# XDS100V2_EMULATOR.net
KiCad netlist of a schematic drawn in Altium Designer
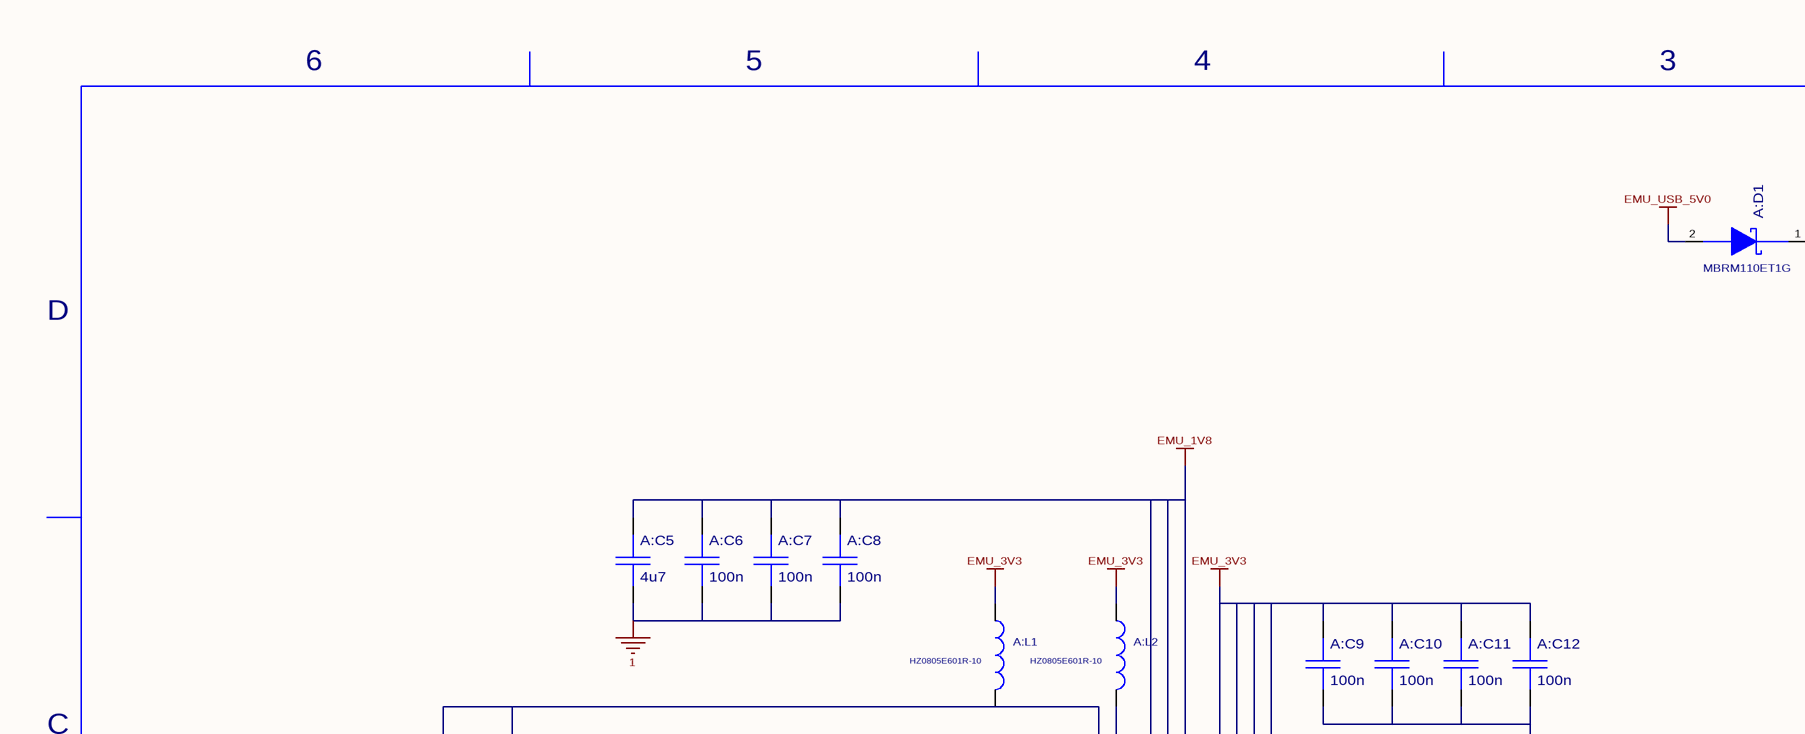
[diagram p0: XDS100V2_EMULATOR.SchDoc, top left]
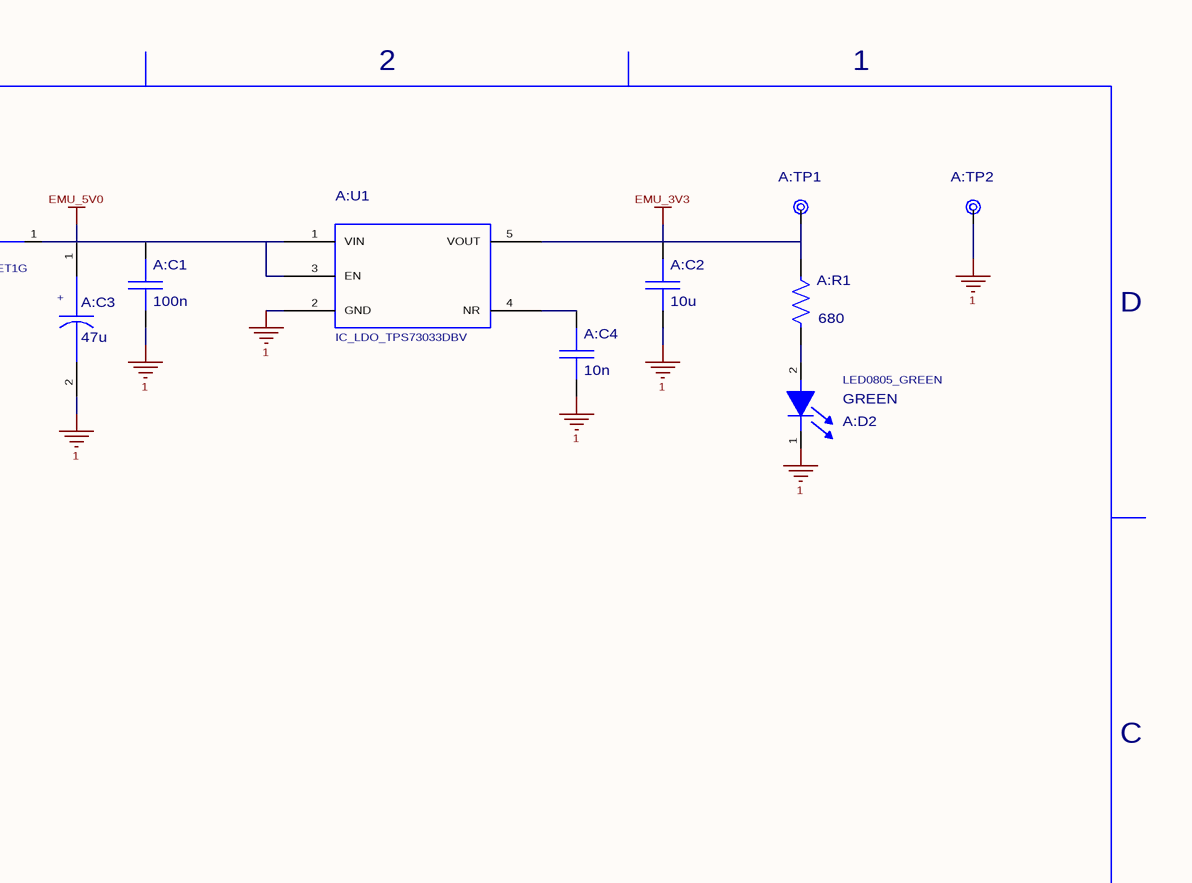
[diagram p1: XDS100V2_EMULATOR.SchDoc, top right]
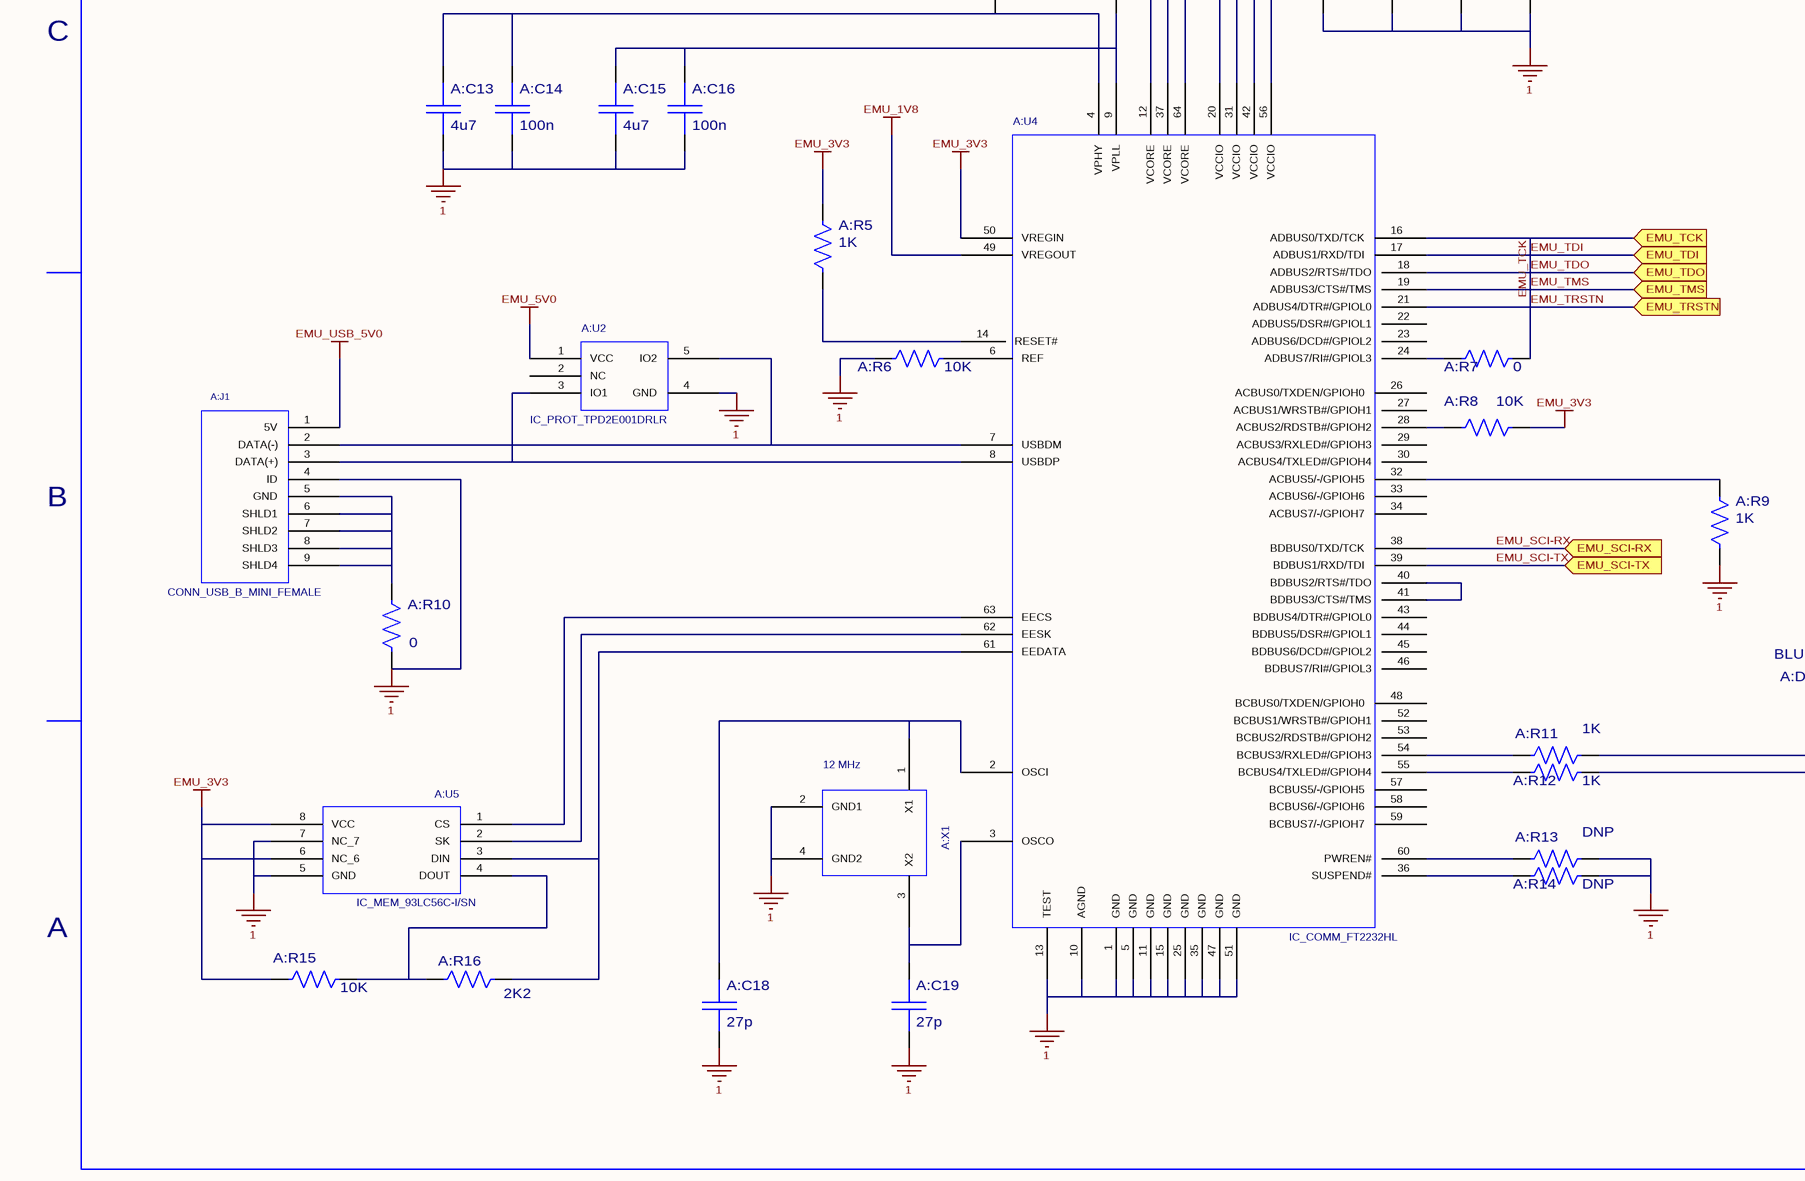
[diagram p2: XDS100V2_EMULATOR.SchDoc, bottom left]
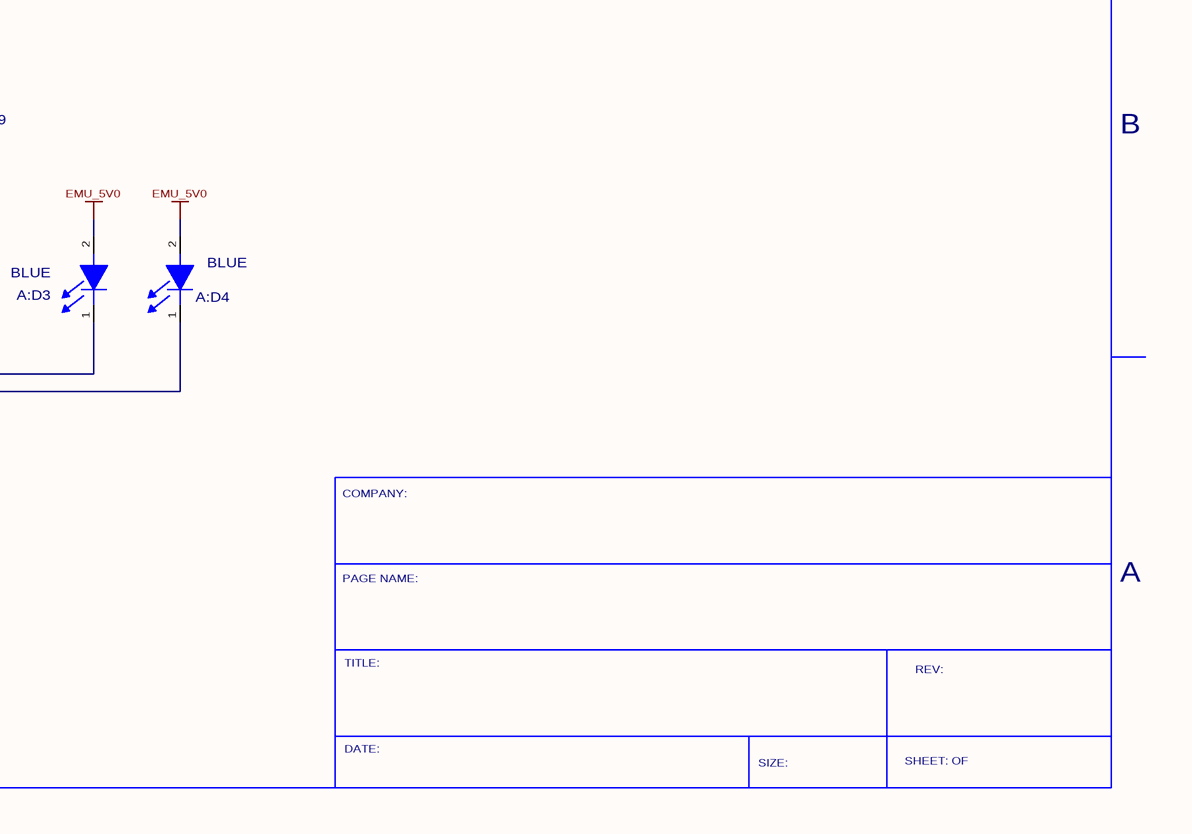
[diagram p3: XDS100V2_EMULATOR.SchDoc, bottom right]

(export (version "E")
  (design (tool "Eeschema 10.0.6"))
  (components
    (comp (ref "A:C1")
      (value "100n")
      (footprint "C0402")
      (description "CAP CER 16V 10% X7R 0402")
      (fields (field (name "Comment") "C0402_16V_X7R"))
      (libsource (lib "*") (part "C0402_16V_X7R"))
    )
    (comp (ref "A:C2")
      (value "10u")
      (footprint "C0603")
      (description "CAP CER 6.3V 20% X5R 0603")
      (fields (field (name "Comment") "C0603_16V_X7R"))
      (libsource (lib "*") (part "C0603_16V_X7R"))
    )
    (comp (ref "A:C3")
      (value "47u")
      (footprint "C0805P")
      (description "CAP TANT 20% 0805 6.3V")
      (fields (field (name "PART NUMBER") "TCTP0J476M8R") (field (name "Comment") "C0805_10V_TANT"))
      (libsource (lib "*") (part "C0805_10V_TANT"))
    )
    (comp (ref "A:C4")
      (value "10n")
      (footprint "C0402")
      (description "CAP CER 16V 10% X7R 0402")
      (fields (field (name "Comment") "C0402_16V_X7R"))
      (libsource (lib "*") (part "C0402_16V_X7R"))
    )
    (comp (ref "A:C5")
      (value "4u7")
      (footprint "C0603")
      (description "CAP CER 6.3V 10% X5R 0603")
      (fields (field (name "Comment") "C0603_16V_X7R"))
      (libsource (lib "*") (part "C0603_16V_X7R"))
    )
    (comp (ref "A:C6")
      (value "100n")
      (footprint "C0402")
      (description "CAP CER 16V 10% X7R 0402")
      (fields (field (name "Comment") "C0402_16V_X7R"))
      (libsource (lib "*") (part "C0402_16V_X7R"))
    )
    (comp (ref "A:C7")
      (value "100n")
      (footprint "C0402")
      (description "CAP CER 16V 10% X7R 0402")
      (fields (field (name "Comment") "C0402_16V_X7R"))
      (libsource (lib "*") (part "C0402_16V_X7R"))
    )
    (comp (ref "A:C8")
      (value "100n")
      (footprint "C0402")
      (description "CAP CER 16V 10% X7R 0402")
      (fields (field (name "Comment") "C0402_16V_X7R"))
      (libsource (lib "*") (part "C0402_16V_X7R"))
    )
    (comp (ref "A:C9")
      (value "100n")
      (footprint "C0402")
      (description "CAP CER 16V 10% X7R 0402")
      (fields (field (name "Comment") "C0402_16V_X7R"))
      (libsource (lib "*") (part "C0402_16V_X7R"))
    )
    (comp (ref "A:C10")
      (value "100n")
      (footprint "C0402")
      (description "CAP CER 16V 10% X7R 0402")
      (fields (field (name "Comment") "C0402_16V_X7R"))
      (libsource (lib "*") (part "C0402_16V_X7R"))
    )
    (comp (ref "A:C11")
      (value "100n")
      (footprint "C0402")
      (description "CAP CER 16V 10% X7R 0402")
      (fields (field (name "Comment") "C0402_16V_X7R"))
      (libsource (lib "*") (part "C0402_16V_X7R"))
    )
    (comp (ref "A:C12")
      (value "100n")
      (footprint "C0402")
      (description "CAP CER 16V 10% X7R 0402")
      (fields (field (name "Comment") "C0402_16V_X7R"))
      (libsource (lib "*") (part "C0402_16V_X7R"))
    )
    (comp (ref "A:C13")
      (value "4u7")
      (footprint "C0603")
      (description "CAP CER 6.3V 10% X5R 0603")
      (fields (field (name "Comment") "C0603_16V_X7R"))
      (libsource (lib "*") (part "C0603_16V_X7R"))
    )
    (comp (ref "A:C14")
      (value "100n")
      (footprint "C0402")
      (description "CAP CER 16V 10% X7R 0402")
      (fields (field (name "Comment") "C0402_16V_X7R"))
      (libsource (lib "*") (part "C0402_16V_X7R"))
    )
    (comp (ref "A:C15")
      (value "4u7")
      (footprint "C0603")
      (description "CAP CER 6.3V 10% X5R 0603")
      (fields (field (name "Comment") "C0603_16V_X7R"))
      (libsource (lib "*") (part "C0603_16V_X7R"))
    )
    (comp (ref "A:C16")
      (value "100n")
      (footprint "C0402")
      (description "CAP CER 16V 10% X7R 0402")
      (fields (field (name "Comment") "C0402_16V_X7R"))
      (libsource (lib "*") (part "C0402_16V_X7R"))
    )
    (comp (ref "A:C18")
      (value "27p")
      (footprint "C0402")
      (description "CAP CER 50V NP0 0402")
      (fields (field (name "Comment") "C0402_50V_NP0"))
      (libsource (lib "*") (part "C0402_50V_NP0"))
    )
    (comp (ref "A:C19")
      (value "27p")
      (footprint "C0402")
      (description "CAP CER 50V NP0 0402")
      (fields (field (name "Comment") "C0402_50V_NP0"))
      (libsource (lib "*") (part "C0402_50V_NP0"))
    )
    (comp (ref "A:D1")
      (value "DIODE_SCHOTTKY_MBRM110ET1G")
      (footprint "DO-216AA")
      (description "DIODE SCHOTTKY 10V 1A POWERMITE")
      (fields (field (name "PART NUMBER") "MBRM110ET1G") (field (name "MANUFACTURER") "On Semiconductor"))
      (libsource (lib "*") (part "DIODE_SCHOTTKY_MBRM110ET1G"))
    )
    (comp (ref "A:D2")
      (value "LED0805_GREEN")
      (footprint "LED0805")
      (description "LED GREEN 0805 SMD, Diffused, 567nm")
      (fields (field (name "ALTIUM_VALUE") "GREEN"))
      (libsource (lib "*") (part "LED0805_GREEN"))
    )
    (comp (ref "A:D3")
      (value "BLUE")
      (footprint "LED0805")
      (description "LED BLUE 0805 SMD, Clear, 470nm")
      (fields (field (name "Comment") "LED0805_BLUE"))
      (libsource (lib "*") (part "LED0805_BLUE"))
    )
    (comp (ref "A:D4")
      (value "BLUE")
      (footprint "LED0805")
      (description "LED BLUE 0805 SMD, Clear, 470nm")
      (fields (field (name "Comment") "LED0805_BLUE"))
      (libsource (lib "*") (part "LED0805_BLUE"))
    )
    (comp (ref "A:J1")
      (value "CONN_USB_B_MINI_FEMALE")
      (footprint "CONN_USB_B_MINI_FEMALE")
      (description "CONN RECEPT MINI USB2.0 5POS")
      (fields (field (name "PART NUMBER") "UX60-MB-5ST"))
      (libsource (lib "*") (part "CONN_USB_B_MINI_FEMALE"))
    )
    (comp (ref "A:L1")
      (value "L0805_HZ0805E601R-10")
      (footprint "L0805")
      (description "FERRITE 500MA 600 OHM 0805 SMD")
      (fields (field (name "PART NUMBER") "HZ0805E601R-10"))
      (libsource (lib "*") (part "L0805_HZ0805E601R-10"))
    )
    (comp (ref "A:L2")
      (value "L0805_HZ0805E601R-10")
      (footprint "L0805")
      (description "FERRITE 500MA 600 OHM 0805 SMD")
      (fields (field (name "PART NUMBER") "HZ0805E601R-10"))
      (libsource (lib "*") (part "L0805_HZ0805E601R-10"))
    )
    (comp (ref "A:R1")
      (value "680")
      (footprint "R0402")
      (description "RES 1/16W 5% 0402 SMD")
      (fields (field (name "Comment") "R0402_5%"))
      (libsource (lib "") (part "R0402_5%_1"))
    )
    (comp (ref "A:R5")
      (value "1K")
      (footprint "R0402")
      (description "RES 1/16W 5% 0402 SMD")
      (fields (field (name "Comment") "R0402_5%"))
      (libsource (lib "") (part "R0402_5%_1"))
    )
    (comp (ref "A:R6")
      (value "10K")
      (footprint "R0402")
      (description "RES 1/16W 5% 0402 SMD")
      (fields (field (name "Comment") "R0402_5%"))
      (libsource (lib "*") (part "R0402_5%"))
    )
    (comp (ref "A:R7")
      (value "0")
      (footprint "R0402")
      (description "RES 1/16W 5% 0402 SMD")
      (fields (field (name "Comment") "R0402_5%"))
      (libsource (lib "*") (part "R0402_5%"))
    )
    (comp (ref "A:R8")
      (value "10K")
      (footprint "R0402")
      (description "RES 1/16W 5% 0402 SMD")
      (fields (field (name "Comment") "R0402_5%"))
      (libsource (lib "*") (part "R0402_5%"))
    )
    (comp (ref "A:R9")
      (value "1K")
      (footprint "R0402")
      (description "RES 1/16W 5% 0402 SMD")
      (fields (field (name "Comment") "R0402_5%"))
      (libsource (lib "") (part "R0402_5%_1"))
    )
    (comp (ref "A:R10")
      (value "0")
      (footprint "R0402")
      (description "RES 1/16W 5% 0402 SMD")
      (fields (field (name "Comment") "R0402_5%"))
      (libsource (lib "") (part "R0402_5%_1"))
    )
    (comp (ref "A:R11")
      (value "1K")
      (footprint "R0402")
      (description "RES 1/16W 5% 0402 SMD")
      (fields (field (name "Comment") "R0402_5%"))
      (libsource (lib "*") (part "R0402_5%"))
    )
    (comp (ref "A:R12")
      (value "1K")
      (footprint "R0402")
      (description "RES 1/16W 5% 0402 SMD")
      (fields (field (name "Comment") "R0402_5%"))
      (libsource (lib "*") (part "R0402_5%"))
    )
    (comp (ref "A:R13")
      (value "DNP")
      (footprint "R0402")
      (description "RES 1/16W 5% 0402 SMD")
      (fields (field (name "Comment") "R0402_5%"))
      (libsource (lib "*") (part "R0402_5%"))
    )
    (comp (ref "A:R14")
      (value "DNP")
      (footprint "R0402")
      (description "RES 1/16W 5% 0402 SMD")
      (fields (field (name "Comment") "R0402_5%"))
      (libsource (lib "*") (part "R0402_5%"))
    )
    (comp (ref "A:R15")
      (value "10K")
      (footprint "R0402")
      (description "RES 1/16W 5% 0402 SMD")
      (fields (field (name "Comment") "R0402_5%"))
      (libsource (lib "*") (part "R0402_5%"))
    )
    (comp (ref "A:R16")
      (value "2K2")
      (footprint "R0402")
      (description "RES 1/16W 5% 0402 SMD")
      (fields (field (name "Comment") "R0402_5%"))
      (libsource (lib "") (part "R0402_5%_1"))
    )
    (comp (ref "A:TP1")
      (value "VIA_20_40")
      (footprint "VIA_20_40")
      (description "Via, 20 ID, 40 OD (mil)")
      (libsource (lib "*") (part "VIA_20_40"))
    )
    (comp (ref "A:TP2")
      (value "VIA_20_40")
      (footprint "VIA_20_40")
      (description "Via, 20 ID, 40 OD (mil)")
      (libsource (lib "*") (part "VIA_20_40"))
    )
    (comp (ref "A:U1")
      (value "IC_LDO_TPS73033DBV")
      (footprint "SOT-23-5")
      (description "IC LDO REG HI-PSRR 3.3V SOT23-5")
      (fields (field (name "PART NUMBER") "TPS73033DBV"))
      (libsource (lib "*") (part "IC_LDO_TPS73033DBV"))
    )
    (comp (ref "A:U2")
      (value "IC_PROT_TPD2E001DRLR")
      (footprint "SOT-553-5")
      (description "IC ESD-PROT ARRAY 2CH SOT-5")
      (fields (field (name "PART NUMBER") "TPD2E001DRLR"))
      (libsource (lib "*") (part "IC_PROT_TPD2E001DRLR"))
    )
    (comp (ref "A:U4")
      (value "IC_COMM_FT2232HL")
      (footprint "QFN-64")
      (description "IC USB HS DUAL UART/FIFO 64-QFN")
      (fields (field (name "PART NUMBER") "FT2232HL"))
      (libsource (lib "*") (part "IC_COMM_FT2232HL"))
    )
    (comp (ref "A:U5")
      (value "IC_MEM_93LC56C-I/SN")
      (footprint "SOIC-8")
      (description "IC EEPROM 2KBIT 3MHZ 8SOIC")
      (fields (field (name "PART NUMBER") "93LC56C-I/SN"))
      (libsource (lib "*") (part "IC_MEM_93LC56C-I/SN"))
    )
    (comp (ref "A:X1")
      (value "12 MHz")
      (footprint "OSC_ECS-120-20-30B")
      (description "CRYSTAL 12.000 MHZ 20PF SMD")
      (fields
        (field (name "PART NUMBER") "ECS-120-20-30B-TR")
        (field (name "Comment") "OSC_ECS-120-20-30B-TR")
      )
      (libsource (lib "*") (part "OSC_ECS-120-20-30B-TR"))
    )
  )
  (nets
    (net (code "1") (name "/EMU_SCI-RX") (class "Default")
      (node (ref "A:U4") (pin "38") (pinfunction "BDBUS0/TXD/TCK_38") (pintype "passive"))
    )
    (net (code "2") (name "/EMU_SCI-TX") (class "Default")
      (node (ref "A:U4") (pin "39") (pinfunction "BDBUS1/RXD/TDI_39") (pintype "passive"))
    )
    (net (code "3") (name "/EMU_TCK") (class "Default")
      (node (ref "A:R7") (pin "2") (pinfunction "2_2") (pintype "passive"))
      (node (ref "A:U4") (pin "16") (pinfunction "ADBUS0/TXD/TCK_16") (pintype "passive"))
      (node (ref "A:U4") (pin "17") (pinfunction "ADBUS1/RXD/TDI_17") (pintype "passive"))
      (node (ref "A:U4") (pin "18") (pinfunction "ADBUS2/RTS#/TDO_18") (pintype "passive"))
      (node (ref "A:U4") (pin "19") (pinfunction "ADBUS3/CTS#/TMS_19") (pintype "passive"))
      (node (ref "A:U4") (pin "21") (pinfunction "ADBUS4/DTR#/GPIOL0_21") (pintype "passive"))
    )
    (net (code "4") (name "1") (class "Default")
      (node (ref "A:C1") (pin "1") (pinfunction "1_1") (pintype "passive"))
      (node (ref "A:C10") (pin "1") (pinfunction "1_1") (pintype "passive"))
      (node (ref "A:C11") (pin "1") (pinfunction "1_1") (pintype "passive"))
      (node (ref "A:C12") (pin "1") (pinfunction "1_1") (pintype "passive"))
      (node (ref "A:C13") (pin "1") (pinfunction "1_1") (pintype "passive"))
      (node (ref "A:C14") (pin "1") (pinfunction "1_1") (pintype "passive"))
      (node (ref "A:C15") (pin "1") (pinfunction "1_1") (pintype "passive"))
      (node (ref "A:C16") (pin "1") (pinfunction "1_1") (pintype "passive"))
      (node (ref "A:C18") (pin "1") (pinfunction "1_1") (pintype "passive"))
      (node (ref "A:C19") (pin "1") (pinfunction "1_1") (pintype "passive"))
      (node (ref "A:C2") (pin "1") (pinfunction "1_1") (pintype "passive"))
      (node (ref "A:C3") (pin "2") (pinfunction "2_2") (pintype "passive"))
      (node (ref "A:C4") (pin "1") (pinfunction "1_1") (pintype "passive"))
      (node (ref "A:C5") (pin "1") (pinfunction "1_1") (pintype "passive"))
      (node (ref "A:C6") (pin "1") (pinfunction "1_1") (pintype "passive"))
      (node (ref "A:C7") (pin "1") (pinfunction "1_1") (pintype "passive"))
      (node (ref "A:C8") (pin "1") (pinfunction "1_1") (pintype "passive"))
      (node (ref "A:C9") (pin "1") (pinfunction "1_1") (pintype "passive"))
      (node (ref "A:D2") (pin "1") (pinfunction "C_1") (pintype "passive"))
      (node (ref "A:J1") (pin "4") (pinfunction "ID_4") (pintype "passive"))
      (node (ref "A:R10") (pin "2") (pinfunction "2_2") (pintype "passive"))
      (node (ref "A:R13") (pin "2") (pinfunction "2_2") (pintype "passive"))
      (node (ref "A:R14") (pin "2") (pinfunction "2_2") (pintype "passive"))
      (node (ref "A:R6") (pin "1") (pinfunction "1_1") (pintype "passive"))
      (node (ref "A:R9") (pin "2") (pinfunction "2_2") (pintype "passive"))
      (node (ref "A:TP2") (pin "1") (pinfunction "1_1") (pintype "passive"))
      (node (ref "A:U1") (pin "2") (pinfunction "GND_2") (pintype "power_in"))
      (node (ref "A:U2") (pin "4") (pinfunction "GND_4") (pintype "power_in"))
      (node (ref "A:U4") (pin "1") (pinfunction "GND_1") (pintype "power_in"))
      (node (ref "A:U4") (pin "10") (pinfunction "AGND_10") (pintype "passive"))
      (node (ref "A:U4") (pin "11") (pinfunction "GND_11") (pintype "power_in"))
      (node (ref "A:U4") (pin "13") (pinfunction "TEST_13") (pintype "passive"))
      (node (ref "A:U4") (pin "15") (pinfunction "GND_15") (pintype "power_in"))
      (node (ref "A:U4") (pin "25") (pinfunction "GND_25") (pintype "power_in"))
      (node (ref "A:U4") (pin "35") (pinfunction "GND_35") (pintype "power_in"))
      (node (ref "A:U4") (pin "47") (pinfunction "GND_47") (pintype "power_in"))
      (node (ref "A:U4") (pin "5") (pinfunction "GND_5") (pintype "power_in"))
      (node (ref "A:U4") (pin "51") (pinfunction "GND_51") (pintype "power_in"))
      (node (ref "A:U5") (pin "5") (pinfunction "GND_5") (pintype "passive"))
      (node (ref "A:U5") (pin "7") (pinfunction "NC_7_7") (pintype "passive"))
      (node (ref "A:X1") (pin "2") (pinfunction "GND1_2") (pintype "passive"))
      (node (ref "A:X1") (pin "4") (pinfunction "GND2_4") (pintype "passive"))
    )
    (net (code "5") (name "EMU_1V8") (class "Default")
      (node (ref "A:C5") (pin "2") (pinfunction "2_2") (pintype "passive"))
      (node (ref "A:C6") (pin "2") (pinfunction "2_2") (pintype "passive"))
      (node (ref "A:C7") (pin "2") (pinfunction "2_2") (pintype "passive"))
      (node (ref "A:C8") (pin "2") (pinfunction "2_2") (pintype "passive"))
      (node (ref "A:U4") (pin "12") (pinfunction "VCORE_12") (pintype "power_in"))
      (node (ref "A:U4") (pin "37") (pinfunction "VCORE_37") (pintype "power_in"))
      (node (ref "A:U4") (pin "49") (pinfunction "VREGOUT_49") (pintype "power_in"))
      (node (ref "A:U4") (pin "64") (pinfunction "VCORE_64") (pintype "power_in"))
    )
    (net (code "6") (name "EMU_3V3") (class "Default")
      (node (ref "A:C10") (pin "2") (pinfunction "2_2") (pintype "passive"))
      (node (ref "A:C11") (pin "2") (pinfunction "2_2") (pintype "passive"))
      (node (ref "A:C12") (pin "2") (pinfunction "2_2") (pintype "passive"))
      (node (ref "A:C2") (pin "2") (pinfunction "2_2") (pintype "passive"))
      (node (ref "A:C9") (pin "2") (pinfunction "2_2") (pintype "passive"))
      (node (ref "A:L1") (pin "1") (pinfunction "1_1") (pintype "passive"))
      (node (ref "A:L2") (pin "1") (pinfunction "1_1") (pintype "passive"))
      (node (ref "A:R1") (pin "1") (pinfunction "1_1") (pintype "passive"))
      (node (ref "A:R15") (pin "1") (pinfunction "1_1") (pintype "passive"))
      (node (ref "A:R5") (pin "1") (pinfunction "1_1") (pintype "passive"))
      (node (ref "A:R8") (pin "2") (pinfunction "2_2") (pintype "passive"))
      (node (ref "A:TP1") (pin "1") (pinfunction "1_1") (pintype "passive"))
      (node (ref "A:U1") (pin "5") (pinfunction "VOUT_5") (pintype "passive"))
      (node (ref "A:U4") (pin "20") (pinfunction "VCCIO_20") (pintype "power_in"))
      (node (ref "A:U4") (pin "31") (pinfunction "VCCIO_31") (pintype "power_in"))
      (node (ref "A:U4") (pin "42") (pinfunction "VCCIO_42") (pintype "power_in"))
      (node (ref "A:U4") (pin "50") (pinfunction "VREGIN_50") (pintype "power_in"))
      (node (ref "A:U4") (pin "56") (pinfunction "VCCIO_56") (pintype "power_in"))
      (node (ref "A:U5") (pin "6") (pinfunction "NC_6_6") (pintype "passive"))
      (node (ref "A:U5") (pin "8") (pinfunction "VCC_8") (pintype "passive"))
    )
    (net (code "7") (name "EMU_5V0") (class "Default")
      (node (ref "A:C1") (pin "2") (pinfunction "2_2") (pintype "passive"))
      (node (ref "A:C3") (pin "1") (pinfunction "1_1") (pintype "passive"))
      (node (ref "A:D1") (pin "1") (pinfunction "C_1") (pintype "passive"))
      (node (ref "A:D3") (pin "2") (pinfunction "A_2") (pintype "passive"))
      (node (ref "A:D4") (pin "2") (pinfunction "A_2") (pintype "passive"))
      (node (ref "A:U1") (pin "1") (pinfunction "VIN_1") (pintype "passive"))
      (node (ref "A:U1") (pin "3") (pinfunction "EN_3") (pintype "passive"))
      (node (ref "A:U2") (pin "1") (pinfunction "VCC_1") (pintype "power_in"))
    )
    (net (code "8") (name "EMU_USB_5V0") (class "Default")
      (node (ref "A:D1") (pin "2") (pinfunction "A_2") (pintype "passive"))
      (node (ref "A:J1") (pin "1") (pinfunction "5V_1") (pintype "power_in"))
    )
    (net (code "9") (name "Net-(A:D2-A)") (class "Default")
      (node (ref "A:D2") (pin "2") (pinfunction "A_2") (pintype "passive"))
      (node (ref "A:R1") (pin "2") (pinfunction "2_2") (pintype "passive"))
    )
    (net (code "10") (name "Net-(A:D3-C)") (class "Default")
      (node (ref "A:D3") (pin "1") (pinfunction "C_1") (pintype "passive"))
      (node (ref "A:R11") (pin "2") (pinfunction "2_2") (pintype "passive"))
    )
    (net (code "11") (name "Net-(A:D4-C)") (class "Default")
      (node (ref "A:D4") (pin "1") (pinfunction "C_1") (pintype "passive"))
      (node (ref "A:R12") (pin "2") (pinfunction "2_2") (pintype "passive"))
    )
    (net (code "12") (name "Net-(A:J1-DATA(+))") (class "Default")
      (node (ref "A:J1") (pin "3") (pinfunction "DATA(+)_3") (pintype "passive"))
      (node (ref "A:U2") (pin "3") (pinfunction "IO1_3") (pintype "passive"))
      (node (ref "A:U4") (pin "8") (pinfunction "USBDP_8") (pintype "passive"))
    )
    (net (code "13") (name "Net-(A:J1-DATA(-))") (class "Default")
      (node (ref "A:J1") (pin "2") (pinfunction "DATA(-)_2") (pintype "passive"))
      (node (ref "A:U2") (pin "5") (pinfunction "IO2_5") (pintype "passive"))
      (node (ref "A:U4") (pin "7") (pinfunction "USBDM_7") (pintype "passive"))
    )
    (net (code "14") (name "Net-(A:J1-GND)") (class "Default")
      (node (ref "A:J1") (pin "5") (pinfunction "GND_5") (pintype "passive"))
      (node (ref "A:J1") (pin "6") (pinfunction "SHLD1_6") (pintype "passive"))
      (node (ref "A:J1") (pin "7") (pinfunction "SHLD2_7") (pintype "passive"))
      (node (ref "A:J1") (pin "8") (pinfunction "SHLD3_8") (pintype "passive"))
      (node (ref "A:J1") (pin "9") (pinfunction "SHLD4_9") (pintype "passive"))
      (node (ref "A:R10") (pin "1") (pinfunction "1_1") (pintype "passive"))
    )
    (net (code "15") (name "Net-(A:U1-NR)") (class "Default")
      (node (ref "A:C4") (pin "2") (pinfunction "2_2") (pintype "passive"))
      (node (ref "A:U1") (pin "4") (pinfunction "NR_4") (pintype "passive"))
    )
    (net (code "16") (name "Net-(A:U4-ACBUS2{slash}RDSTB#{slash}GPIOH2)") (class "Default")
      (node (ref "A:R8") (pin "1") (pinfunction "1_1") (pintype "passive"))
      (node (ref "A:U4") (pin "28") (pinfunction "ACBUS2/RDSTB#/GPIOH2_28") (pintype "passive"))
    )
    (net (code "17") (name "Net-(A:U4-ACBUS5{slash}-{slash}GPIOH5)") (class "Default")
      (node (ref "A:R9") (pin "1") (pinfunction "1_1") (pintype "passive"))
      (node (ref "A:U4") (pin "32") (pinfunction "ACBUS5/-/GPIOH5_32") (pintype "passive"))
    )
    (net (code "18") (name "Net-(A:U4-ADBUS7{slash}RI#{slash}GPIOL3)") (class "Default")
      (node (ref "A:R7") (pin "1") (pinfunction "1_1") (pintype "passive"))
      (node (ref "A:U4") (pin "24") (pinfunction "ADBUS7/RI#/GPIOL3_24") (pintype "passive"))
    )
    (net (code "19") (name "Net-(A:U4-BCBUS3{slash}RXLED#{slash}GPIOH3)") (class "Default")
      (node (ref "A:R11") (pin "1") (pinfunction "1_1") (pintype "passive"))
      (node (ref "A:U4") (pin "54") (pinfunction "BCBUS3/RXLED#/GPIOH3_54") (pintype "passive"))
    )
    (net (code "20") (name "Net-(A:U4-BCBUS4{slash}TXLED#{slash}GPIOH4)") (class "Default")
      (node (ref "A:R12") (pin "1") (pinfunction "1_1") (pintype "passive"))
      (node (ref "A:U4") (pin "55") (pinfunction "BCBUS4/TXLED#/GPIOH4_55") (pintype "passive"))
    )
    (net (code "21") (name "Net-(A:U4-BDBUS2{slash}RTS#{slash}TDO)") (class "Default")
      (node (ref "A:U4") (pin "40") (pinfunction "BDBUS2/RTS#/TDO_40") (pintype "passive"))
      (node (ref "A:U4") (pin "41") (pinfunction "BDBUS3/CTS#/TMS_41") (pintype "passive"))
    )
    (net (code "22") (name "Net-(A:U4-EECS)") (class "Default")
      (node (ref "A:U4") (pin "63") (pinfunction "EECS_63") (pintype "passive"))
      (node (ref "A:U5") (pin "1") (pinfunction "CS_1") (pintype "passive"))
    )
    (net (code "23") (name "Net-(A:U4-EEDATA)") (class "Default")
      (node (ref "A:R16") (pin "2") (pinfunction "2_2") (pintype "passive"))
      (node (ref "A:U4") (pin "61") (pinfunction "EEDATA_61") (pintype "passive"))
      (node (ref "A:U5") (pin "3") (pinfunction "DIN_3") (pintype "passive"))
    )
    (net (code "24") (name "Net-(A:U4-EESK)") (class "Default")
      (node (ref "A:U4") (pin "62") (pinfunction "EESK_62") (pintype "passive"))
      (node (ref "A:U5") (pin "2") (pinfunction "SK_2") (pintype "passive"))
    )
    (net (code "25") (name "Net-(A:U4-OSCI)") (class "Default")
      (node (ref "A:C18") (pin "2") (pinfunction "2_2") (pintype "passive"))
      (node (ref "A:U4") (pin "2") (pinfunction "OSCI_2") (pintype "passive"))
      (node (ref "A:X1") (pin "1") (pinfunction "X1_1") (pintype "passive"))
    )
    (net (code "26") (name "Net-(A:U4-OSCO)") (class "Default")
      (node (ref "A:C19") (pin "2") (pinfunction "2_2") (pintype "passive"))
      (node (ref "A:U4") (pin "3") (pinfunction "OSCO_3") (pintype "passive"))
      (node (ref "A:X1") (pin "3") (pinfunction "X2_3") (pintype "passive"))
    )
    (net (code "27") (name "Net-(A:U4-PWREN#)") (class "Default")
      (node (ref "A:R13") (pin "1") (pinfunction "1_1") (pintype "passive"))
      (node (ref "A:U4") (pin "60") (pinfunction "PWREN#_60") (pintype "passive"))
    )
    (net (code "28") (name "Net-(A:U4-REF)") (class "Default")
      (node (ref "A:R6") (pin "2") (pinfunction "2_2") (pintype "passive"))
      (node (ref "A:U4") (pin "6") (pinfunction "REF_6") (pintype "passive"))
    )
    (net (code "29") (name "Net-(A:U4-RESET#)") (class "Default")
      (node (ref "A:R5") (pin "2") (pinfunction "2_2") (pintype "passive"))
      (node (ref "A:U4") (pin "14") (pinfunction "RESET#_14") (pintype "passive"))
    )
    (net (code "30") (name "Net-(A:U4-SUSPEND#)") (class "Default")
      (node (ref "A:R14") (pin "1") (pinfunction "1_1") (pintype "passive"))
      (node (ref "A:U4") (pin "36") (pinfunction "SUSPEND#_36") (pintype "passive"))
    )
    (net (code "31") (name "Net-(A:U4-VPHY)") (class "Default")
      (node (ref "A:C13") (pin "2") (pinfunction "2_2") (pintype "passive"))
      (node (ref "A:C14") (pin "2") (pinfunction "2_2") (pintype "passive"))
      (node (ref "A:L1") (pin "2") (pinfunction "2_2") (pintype "passive"))
      (node (ref "A:U4") (pin "4") (pinfunction "VPHY_4") (pintype "passive"))
    )
    (net (code "32") (name "Net-(A:U4-VPLL)") (class "Default")
      (node (ref "A:C15") (pin "2") (pinfunction "2_2") (pintype "passive"))
      (node (ref "A:C16") (pin "2") (pinfunction "2_2") (pintype "passive"))
      (node (ref "A:L2") (pin "2") (pinfunction "2_2") (pintype "passive"))
      (node (ref "A:U4") (pin "9") (pinfunction "VPLL_9") (pintype "passive"))
    )
    (net (code "33") (name "Net-(A:U5-DOUT)") (class "Default")
      (node (ref "A:R15") (pin "2") (pinfunction "2_2") (pintype "passive"))
      (node (ref "A:R16") (pin "1") (pinfunction "1_1") (pintype "passive"))
      (node (ref "A:U5") (pin "4") (pinfunction "DOUT_4") (pintype "passive"))
    )
    (net (code "34") (name "unconnected-(A:U2-NC-Pad2)") (class "Default")
      (node (ref "A:U2") (pin "2") (pinfunction "NC_2") (pintype "passive"))
    )
    (net (code "35") (name "unconnected-(A:U4-ACBUS0{slash}TXDEN{slash}GPIOH0-Pad26)") (class "Default")
      (node (ref "A:U4") (pin "26") (pinfunction "ACBUS0/TXDEN/GPIOH0_26") (pintype "passive"))
    )
    (net (code "36") (name "unconnected-(A:U4-ACBUS1{slash}WRSTB#{slash}GPIOH1-Pad27)") (class "Default")
      (node (ref "A:U4") (pin "27") (pinfunction "ACBUS1/WRSTB#/GPIOH1_27") (pintype "passive"))
    )
    (net (code "37") (name "unconnected-(A:U4-ACBUS3{slash}RXLED#{slash}GPIOH3-Pad29)") (class "Default")
      (node (ref "A:U4") (pin "29") (pinfunction "ACBUS3/RXLED#/GPIOH3_29") (pintype "passive"))
    )
    (net (code "38") (name "unconnected-(A:U4-ACBUS4{slash}TXLED#{slash}GPIOH4-Pad30)") (class "Default")
      (node (ref "A:U4") (pin "30") (pinfunction "ACBUS4/TXLED#/GPIOH4_30") (pintype "passive"))
    )
    (net (code "39") (name "unconnected-(A:U4-ACBUS6{slash}-{slash}GPIOH6-Pad33)") (class "Default")
      (node (ref "A:U4") (pin "33") (pinfunction "ACBUS6/-/GPIOH6_33") (pintype "passive"))
    )
    (net (code "40") (name "unconnected-(A:U4-ACBUS7{slash}-{slash}GPIOH7-Pad34)") (class "Default")
      (node (ref "A:U4") (pin "34") (pinfunction "ACBUS7/-/GPIOH7_34") (pintype "passive"))
    )
    (net (code "41") (name "unconnected-(A:U4-ADBUS5{slash}DSR#{slash}GPIOL1-Pad22)") (class "Default")
      (node (ref "A:U4") (pin "22") (pinfunction "ADBUS5/DSR#/GPIOL1_22") (pintype "passive"))
    )
    (net (code "42") (name "unconnected-(A:U4-ADBUS6{slash}DCD#{slash}GPIOL2-Pad23)") (class "Default")
      (node (ref "A:U4") (pin "23") (pinfunction "ADBUS6/DCD#/GPIOL2_23") (pintype "passive"))
    )
    (net (code "43") (name "unconnected-(A:U4-BCBUS0{slash}TXDEN{slash}GPIOH0-Pad48)") (class "Default")
      (node (ref "A:U4") (pin "48") (pinfunction "BCBUS0/TXDEN/GPIOH0_48") (pintype "passive"))
    )
    (net (code "44") (name "unconnected-(A:U4-BCBUS1{slash}WRSTB#{slash}GPIOH1-Pad52)") (class "Default")
      (node (ref "A:U4") (pin "52") (pinfunction "BCBUS1/WRSTB#/GPIOH1_52") (pintype "passive"))
    )
    (net (code "45") (name "unconnected-(A:U4-BCBUS2{slash}RDSTB#{slash}GPIOH2-Pad53)") (class "Default")
      (node (ref "A:U4") (pin "53") (pinfunction "BCBUS2/RDSTB#/GPIOH2_53") (pintype "passive"))
    )
    (net (code "46") (name "unconnected-(A:U4-BCBUS5{slash}-{slash}GPIOH5-Pad57)") (class "Default")
      (node (ref "A:U4") (pin "57") (pinfunction "BCBUS5/-/GPIOH5_57") (pintype "passive"))
    )
    (net (code "47") (name "unconnected-(A:U4-BCBUS6{slash}-{slash}GPIOH6-Pad58)") (class "Default")
      (node (ref "A:U4") (pin "58") (pinfunction "BCBUS6/-/GPIOH6_58") (pintype "passive"))
    )
    (net (code "48") (name "unconnected-(A:U4-BCBUS7{slash}-{slash}GPIOH7-Pad59)") (class "Default")
      (node (ref "A:U4") (pin "59") (pinfunction "BCBUS7/-/GPIOH7_59") (pintype "passive"))
    )
    (net (code "49") (name "unconnected-(A:U4-BDBUS4{slash}DTR#{slash}GPIOL0-Pad43)") (class "Default")
      (node (ref "A:U4") (pin "43") (pinfunction "BDBUS4/DTR#/GPIOL0_43") (pintype "passive"))
    )
    (net (code "50") (name "unconnected-(A:U4-BDBUS5{slash}DSR#{slash}GPIOL1-Pad44)") (class "Default")
      (node (ref "A:U4") (pin "44") (pinfunction "BDBUS5/DSR#/GPIOL1_44") (pintype "passive"))
    )
    (net (code "51") (name "unconnected-(A:U4-BDBUS6{slash}DCD#{slash}GPIOL2-Pad45)") (class "Default")
      (node (ref "A:U4") (pin "45") (pinfunction "BDBUS6/DCD#/GPIOL2_45") (pintype "passive"))
    )
    (net (code "52") (name "unconnected-(A:U4-BDBUS7{slash}RI#{slash}GPIOL3-Pad46)") (class "Default")
      (node (ref "A:U4") (pin "46") (pinfunction "BDBUS7/RI#/GPIOL3_46") (pintype "passive"))
    )
  )
)
